# BW1098FFC_TopLevel.net
KiCad netlist of a schematic drawn in Altium Designer
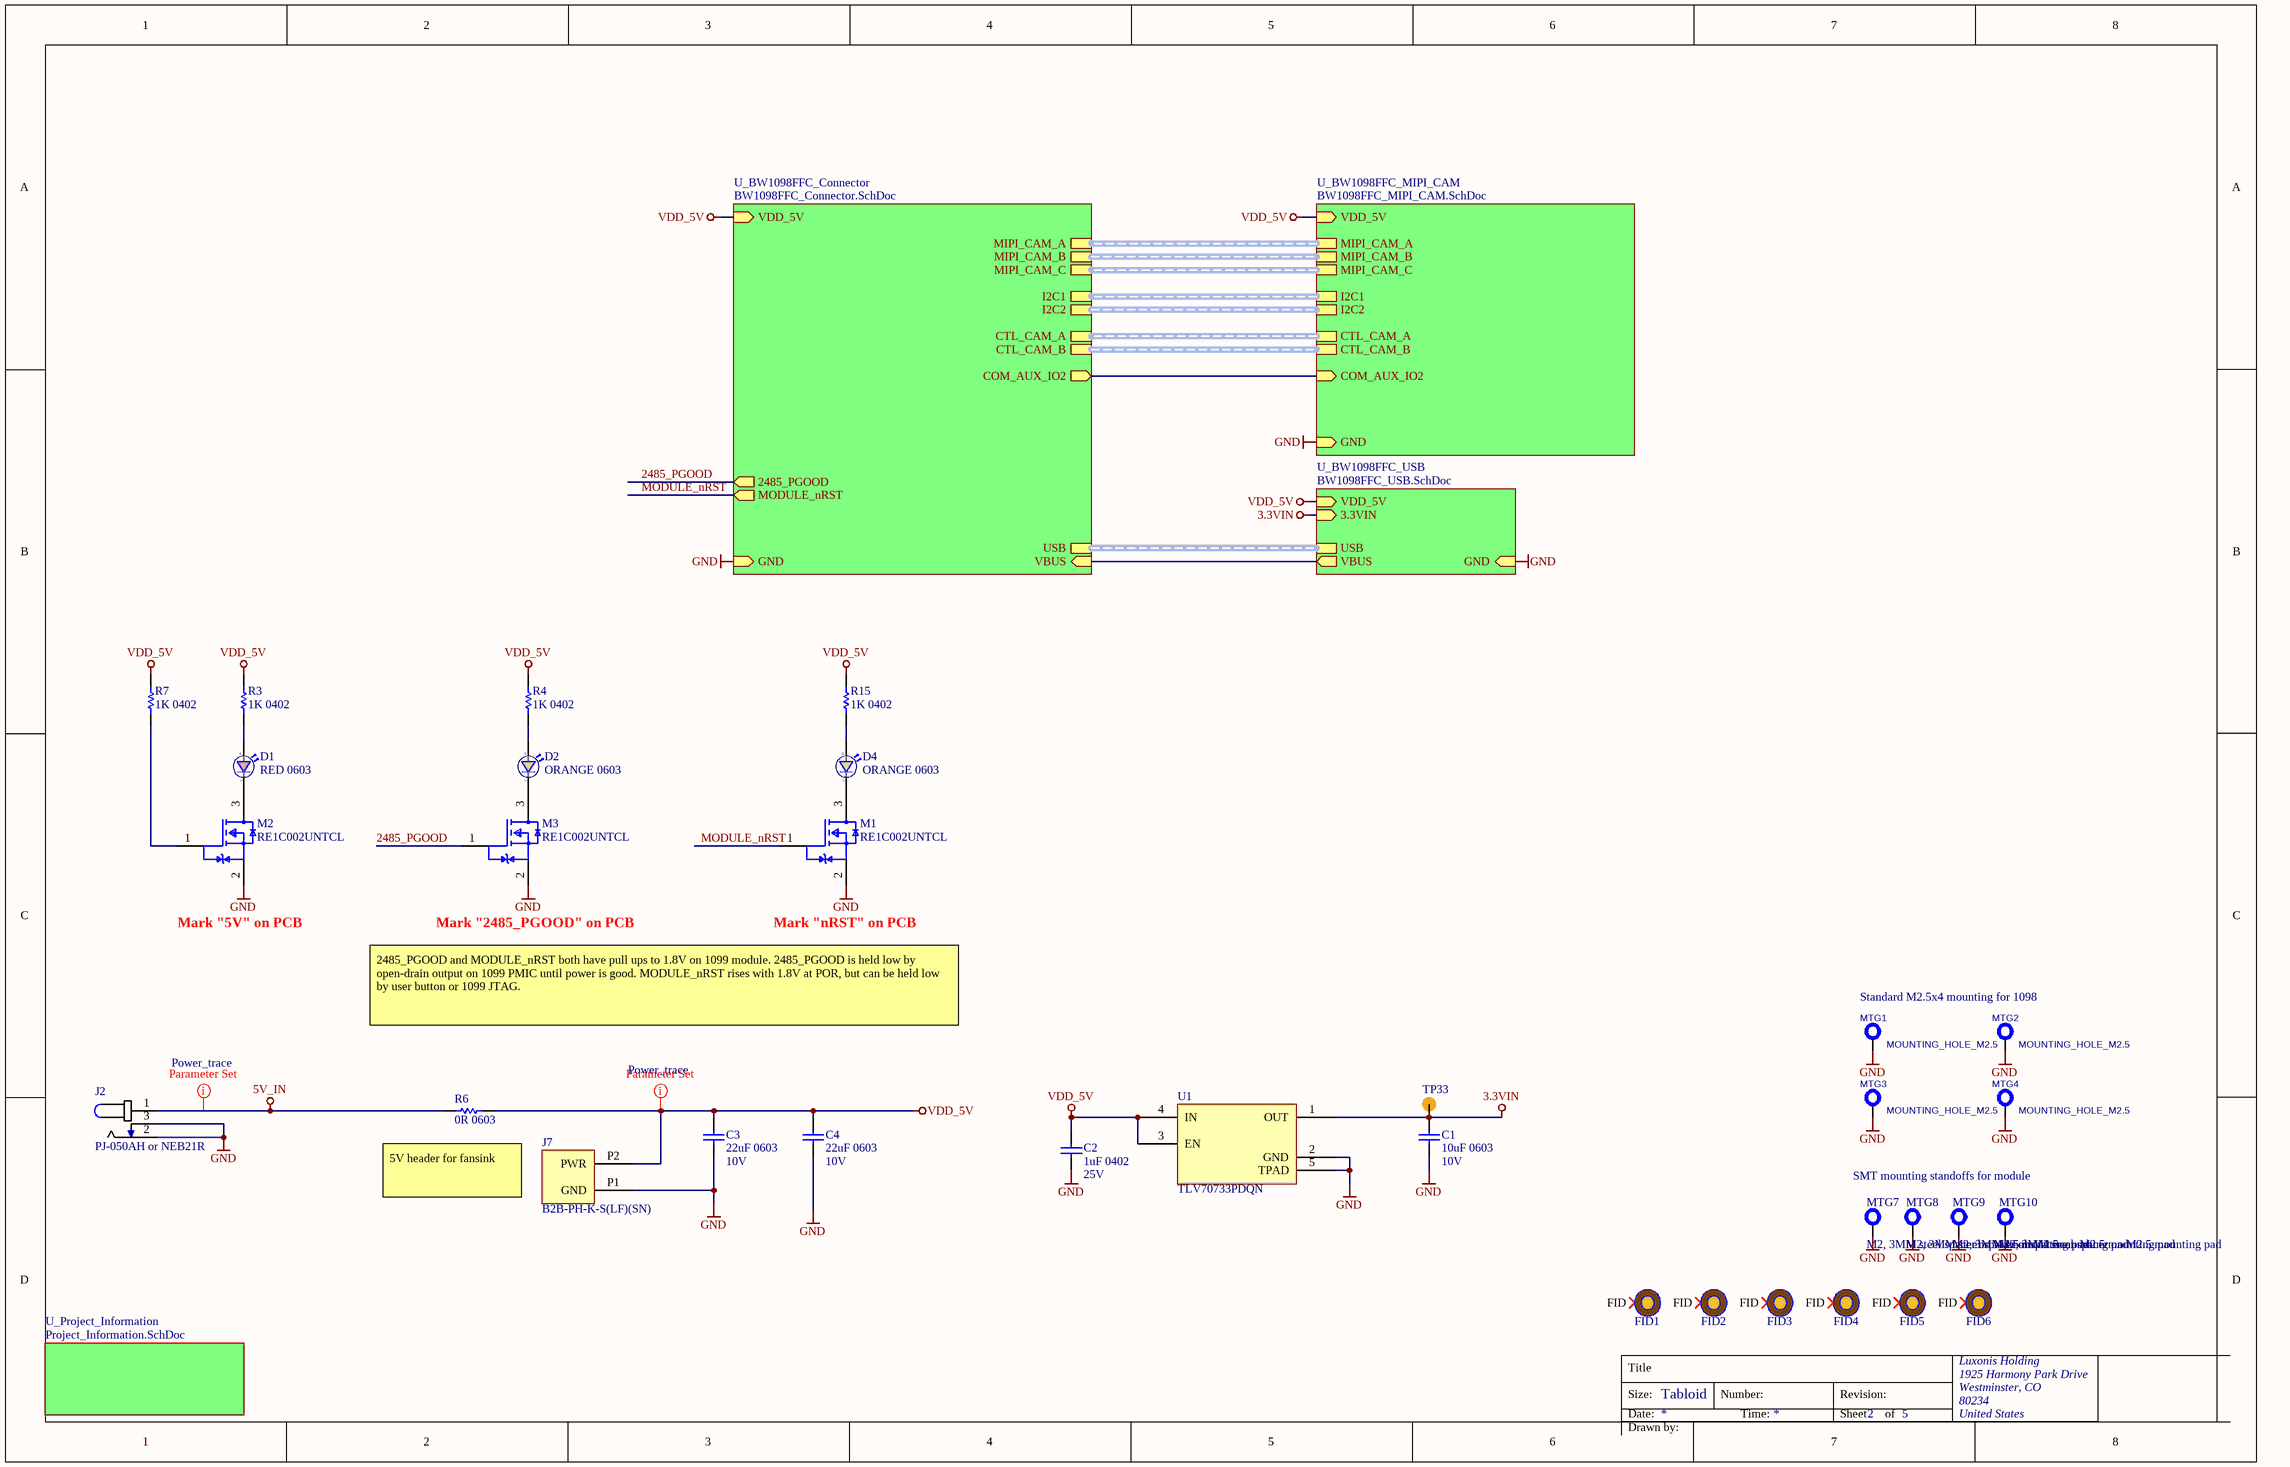
[diagram p0: BW1098FFC_TopLevel.SchDoc]

(export (version "E")
  (design (tool "Eeschema 10.0.6"))
  (components
    (comp (ref "C1")
      (value "10uF 0603")
      (footprint "CAP_Altium_Vault_Generic:CAPC0603(1608)100_N")
      (description "CAP CER 10UF 10V X5R 0603 20%")
      (fields (field (name "TOLERANCE") "20%") (field (name "VOLTAGE RATING") "10V"))
      (libsource (lib "LuxonisMaster") (part "GRM188R61A106ME69D"))
    )
    (comp (ref "C2")
      (value "1uF 0402")
      (footprint "CAP_Altium_Vault_Generic:CAPC0402(1005)70_N")
      (description "CAP CER 1UF 25V X5R 0402 10%")
      (fields
        (field (name "TOLERANCE") "10%")
        (field (name "VOLTAGE") "25V")
        (field (name "VOLTAGE RATING") "25V")
      )
      (libsource (lib "LuxonisMaster") (part "GRM155R61E105KA12D"))
    )
    (comp (ref "C3")
      (value "22uF 0603")
      (footprint "CAP_Altium_Vault_Generic:CAPC0603(1608)100_N")
      (description "CAP CER 22UF 10V X5R 0603 20%")
      (fields (field (name "TOLERANCE") "20%") (field (name "VOLTAGE RATING") "10V"))
      (libsource (lib "LuxonisMaster") (part "GRM188R61A226ME15D"))
    )
    (comp (ref "C4")
      (value "22uF 0603")
      (footprint "CAP_Altium_Vault_Generic:CAPC0603(1608)100_N")
      (description "CAP CER 22UF 10V X5R 0603 20%")
      (fields (field (name "TOLERANCE") "20%") (field (name "VOLTAGE RATING") "10V"))
      (libsource (lib "LuxonisMaster") (part "GRM188R61A226ME15D"))
    )
    (comp (ref "D1")
      (value "RED 0603")
      (footprint "LuxonisMaster:SML_D1xx8W")
      (description "LED RED DIFFUSED 0603 SMD Red 620nm LED Indication - Discrete 2.2V 0603 (1608 Metric)")
      (libsource (lib "LuxonisMaster") (part "SML-D12U8WT86"))
    )
    (comp (ref "D2")
      (value "ORANGE 0603")
      (footprint "LuxonisMaster:SML_D1xx8W")
      (description "LED ORANGE DIFFUSED 0603 SMD Orange 605nm LED Indication - Discrete 2.2V 0603 (1608 Metric)")
      (libsource (lib "LuxonisMaster") (part "SML-D12D8WT86"))
    )
    (comp (ref "D4")
      (value "ORANGE 0603")
      (footprint "LuxonisMaster:SML_D1xx8W")
      (description "LED ORANGE DIFFUSED 0603 SMD Orange 605nm LED Indication - Discrete 2.2V 0603 (1608 Metric)")
      (libsource (lib "LuxonisMaster") (part "SML-D12D8WT86"))
    )
    (comp (ref "FID1")
      (value "FIDUCIAL_ROUND_1MM")
      (footprint "LuxonisMaster:FIDUCIAL_ROUND_1MM")
      (description "Fiducial with various available footprints")
      (libsource (lib "LuxonisMaster") (part "FIDUCIAL"))
    )
    (comp (ref "FID2")
      (value "FIDUCIAL_ROUND_1MM")
      (footprint "LuxonisMaster:FIDUCIAL_ROUND_1MM")
      (description "Fiducial with various available footprints")
      (libsource (lib "LuxonisMaster") (part "FIDUCIAL"))
    )
    (comp (ref "FID3")
      (value "FIDUCIAL_ROUND_1MM")
      (footprint "LuxonisMaster:FIDUCIAL_ROUND_1MM")
      (description "Fiducial with various available footprints")
      (libsource (lib "LuxonisMaster") (part "FIDUCIAL"))
    )
    (comp (ref "FID4")
      (value "FIDUCIAL_ROUND_1MM")
      (footprint "LuxonisMaster:FIDUCIAL_ROUND_1MM")
      (description "Fiducial with various available footprints")
      (libsource (lib "LuxonisMaster") (part "FIDUCIAL"))
    )
    (comp (ref "FID5")
      (value "FIDUCIAL_ROUND_1MM")
      (footprint "LuxonisMaster:FIDUCIAL_ROUND_1MM")
      (description "Fiducial with various available footprints")
      (libsource (lib "LuxonisMaster") (part "FIDUCIAL"))
    )
    (comp (ref "FID6")
      (value "FIDUCIAL_ROUND_1MM")
      (footprint "LuxonisMaster:FIDUCIAL_ROUND_1MM")
      (description "Fiducial with various available footprints")
      (libsource (lib "LuxonisMaster") (part "FIDUCIAL"))
    )
    (comp (ref "J2")
      (value "PJ-050AH or NEB21R")
      (footprint "LuxonisMaster:PJ-050AH/NEB21R_COMBO")
      (description "CONN POWER PIN 2 POS RA PTH Barrel jack 2.1mm x 5.5mm combo footprint")
      (libsource (lib "LuxonisMaster") (part "PJ-050AH/NEB21R_COMBO"))
    )
    (comp (ref "J7")
      (value "B2B-PH-K-S(LF)(SN)")
      (footprint "LuxonisMaster:B2B-PH-K-S(LF)(SN)")
      (description "CONN HEADER VERT 2POS 2MM")
      (libsource (lib "LuxonisMaster") (part "B2B-PH-K-S(LF)(SN)"))
    )
    (comp (ref "M1")
      (value "RE1C002UNTCL")
      (footprint "LuxonisMaster:RE1C002UNTCL")
      (description "MOSFET N-CH 20V 0.2A EMT3")
      (libsource (lib "LuxonisMaster") (part "RE1C002UNTCL"))
    )
    (comp (ref "M2")
      (value "RE1C002UNTCL")
      (footprint "LuxonisMaster:RE1C002UNTCL")
      (description "MOSFET N-CH 20V 0.2A EMT3")
      (libsource (lib "LuxonisMaster") (part "RE1C002UNTCL"))
    )
    (comp (ref "M3")
      (value "RE1C002UNTCL")
      (footprint "LuxonisMaster:RE1C002UNTCL")
      (description "MOSFET N-CH 20V 0.2A EMT3")
      (libsource (lib "LuxonisMaster") (part "RE1C002UNTCL"))
    )
    (comp (ref "MTG1")
      (value "MOUNTING_HOLE_M2.5")
      (footprint "LuxonisMaster:MOUNTING_HOLE_M2.5")
      (description "=CurrentFootprint")
      (libsource (lib "LuxonisMaster") (part "MP_Mounting-Holes"))
    )
    (comp (ref "MTG2")
      (value "MOUNTING_HOLE_M2.5")
      (footprint "LuxonisMaster:MOUNTING_HOLE_M2.5")
      (description "=CurrentFootprint")
      (libsource (lib "LuxonisMaster") (part "MP_Mounting-Holes"))
    )
    (comp (ref "MTG3")
      (value "MOUNTING_HOLE_M2.5")
      (footprint "LuxonisMaster:MOUNTING_HOLE_M2.5")
      (description "=CurrentFootprint")
      (libsource (lib "LuxonisMaster") (part "MP_Mounting-Holes"))
    )
    (comp (ref "MTG4")
      (value "MOUNTING_HOLE_M2.5")
      (footprint "LuxonisMaster:MOUNTING_HOLE_M2.5")
      (description "=CurrentFootprint")
      (libsource (lib "LuxonisMaster") (part "MP_Mounting-Holes"))
    )
    (comp (ref "MTG7")
      (value "M2, 3MM steel spacer on M2.5 mounting pad")
      (footprint "LuxonisMaster:9774030243R")
      (description "MP ROUND STANDOFF M2X0.4 STEEL 3MM")
      (libsource (lib "LuxonisMaster") (part "9774030243R"))
    )
    (comp (ref "MTG8")
      (value "M2, 3MM steel spacer on M2.5 mounting pad")
      (footprint "LuxonisMaster:9774030243R")
      (description "MP ROUND STANDOFF M2X0.4 STEEL 3MM")
      (libsource (lib "LuxonisMaster") (part "9774030243R"))
    )
    (comp (ref "MTG9")
      (value "M2, 3MM steel spacer on M2.5 mounting pad")
      (footprint "LuxonisMaster:9774030243R")
      (description "MP ROUND STANDOFF M2X0.4 STEEL 3MM")
      (libsource (lib "LuxonisMaster") (part "9774030243R"))
    )
    (comp (ref "MTG10")
      (value "M2, 3MM steel spacer on M2.5 mounting pad")
      (footprint "LuxonisMaster:9774030243R")
      (description "MP ROUND STANDOFF M2X0.4 STEEL 3MM")
      (libsource (lib "LuxonisMaster") (part "9774030243R"))
    )
    (comp (ref "R3")
      (value "1K 0402")
      (footprint "RES_Altium_Vault_Generic:RESC0402(1005)_N")
      (fields (field (name "TOLERANCE") "1%"))
      (libsource (lib "LuxonisMaster") (part "RC0402FR-071KL"))
    )
    (comp (ref "R4")
      (value "1K 0402")
      (footprint "RES_Altium_Vault_Generic:RESC0402(1005)_N")
      (fields (field (name "TOLERANCE") "1%"))
      (libsource (lib "LuxonisMaster") (part "RC0402FR-071KL"))
    )
    (comp (ref "R6")
      (value "0R 0603")
      (footprint "RES_Altium_Vault_Generic:RESC0603(1608)_N")
      (fields (field (name "TOLERANCE") "5%"))
      (libsource (lib "LuxonisMaster") (part "CRCW06030000Z0EA"))
    )
    (comp (ref "R7")
      (value "1K 0402")
      (footprint "RES_Altium_Vault_Generic:RESC0402(1005)_N")
      (fields (field (name "TOLERANCE") "1%"))
      (libsource (lib "LuxonisMaster") (part "RC0402FR-071KL"))
    )
    (comp (ref "R15")
      (value "1K 0402")
      (footprint "RES_Altium_Vault_Generic:RESC0402(1005)_N")
      (fields (field (name "TOLERANCE") "1%"))
      (libsource (lib "LuxonisMaster") (part "RC0402FR-071KL"))
    )
    (comp (ref "TP33")
      (value "TP100_200_NS")
      (footprint "LuxonisMaster:TP100_200_NS")
      (libsource (lib "LuxonisMaster") (part "TEST_POINT"))
    )
    (comp (ref "U1")
      (value "TLV70733PDQN")
      (footprint "LuxonisMaster:TLV70733PDQN")
      (description "IC REG LINEAR 3.3V 200MA 4X2SON Linear Voltage Regulator IC  1 Output  200mA 4-X2SON (1x1)")
      (libsource (lib "LuxonisMaster") (part "TLV70733PDQN"))
    )
  )
  (nets
    (net (code "1") (name "/2485_PGOOD") (class "Default")
      (node (ref "M3") (pin "1") (pinfunction "Gate_1") (pintype "passive"))
    )
    (net (code "10") (name "/MODULE_nRST") (class "Default")
      (node (ref "M1") (pin "1") (pinfunction "Gate_1") (pintype "passive"))
    )
    (net (code "13") (name "3.3VIN") (class "Default")
      (node (ref "C1") (pin "2") (pinfunction "2_2") (pintype "passive"))
      (node (ref "TP33") (pin "1") (pintype "passive"))
      (node (ref "U1") (pin "1") (pinfunction "OUT_1") (pintype "power_in"))
    )
    (net (code "14") (name "5V_IN") (class "Default")
      (node (ref "J2") (pin "1") (pinfunction "1_1") (pintype "passive"))
      (node (ref "R6") (pin "1") (pinfunction "1_1") (pintype "passive"))
    )
    (net (code "15") (name "GND") (class "Default")
      (node (ref "C1") (pin "1") (pinfunction "1_1") (pintype "passive"))
      (node (ref "C2") (pin "1") (pinfunction "1_1") (pintype "passive"))
      (node (ref "C3") (pin "1") (pinfunction "1_1") (pintype "passive"))
      (node (ref "C4") (pin "1") (pinfunction "1_1") (pintype "passive"))
      (node (ref "J2") (pin "2") (pinfunction "2_2") (pintype "passive"))
      (node (ref "J2") (pin "3") (pinfunction "3_3") (pintype "passive"))
      (node (ref "J7") (pin "P1") (pinfunction "GND_P1") (pintype "passive"))
      (node (ref "M1") (pin "2") (pinfunction "Source_2") (pintype "passive"))
      (node (ref "M2") (pin "2") (pinfunction "Source_2") (pintype "passive"))
      (node (ref "M3") (pin "2") (pinfunction "Source_2") (pintype "passive"))
      (node (ref "MTG1") (pin "1") (pintype "passive"))
      (node (ref "MTG10") (pin "1") (pintype "passive"))
      (node (ref "MTG2") (pin "1") (pintype "passive"))
      (node (ref "MTG3") (pin "1") (pintype "passive"))
      (node (ref "MTG4") (pin "1") (pintype "passive"))
      (node (ref "MTG7") (pin "1") (pintype "passive"))
      (node (ref "MTG8") (pin "1") (pintype "passive"))
      (node (ref "MTG9") (pin "1") (pintype "passive"))
      (node (ref "U1") (pin "2") (pinfunction "GND_2") (pintype "power_in"))
      (node (ref "U1") (pin "5") (pinfunction "TPAD_5") (pintype "passive"))
    )
    (net (code "16") (name "Net-(D1-A)") (class "Default")
      (node (ref "D1") (pin "2") (pinfunction "A_2") (pintype "passive"))
      (node (ref "R3") (pin "1") (pinfunction "1_1") (pintype "passive"))
    )
    (net (code "17") (name "Net-(D1-C)") (class "Default")
      (node (ref "D1") (pin "1") (pinfunction "C_1") (pintype "passive"))
      (node (ref "M2") (pin "3") (pinfunction "Drain_3") (pintype "passive"))
    )
    (net (code "18") (name "Net-(D2-A)") (class "Default")
      (node (ref "D2") (pin "2") (pinfunction "A_2") (pintype "passive"))
      (node (ref "R4") (pin "1") (pinfunction "1_1") (pintype "passive"))
    )
    (net (code "19") (name "Net-(D2-C)") (class "Default")
      (node (ref "D2") (pin "1") (pinfunction "C_1") (pintype "passive"))
      (node (ref "M3") (pin "3") (pinfunction "Drain_3") (pintype "passive"))
    )
    (net (code "20") (name "Net-(D4-A)") (class "Default")
      (node (ref "D4") (pin "2") (pinfunction "A_2") (pintype "passive"))
      (node (ref "R15") (pin "1") (pinfunction "1_1") (pintype "passive"))
    )
    (net (code "21") (name "Net-(D4-C)") (class "Default")
      (node (ref "D4") (pin "1") (pinfunction "C_1") (pintype "passive"))
      (node (ref "M1") (pin "3") (pinfunction "Drain_3") (pintype "passive"))
    )
    (net (code "22") (name "Net-(M2-Gate)") (class "Default")
      (node (ref "M2") (pin "1") (pinfunction "Gate_1") (pintype "passive"))
      (node (ref "R7") (pin "1") (pinfunction "1_1") (pintype "passive"))
    )
    (net (code "23") (name "VDD_5V") (class "Default")
      (node (ref "C2") (pin "2") (pinfunction "2_2") (pintype "passive"))
      (node (ref "C3") (pin "2") (pinfunction "2_2") (pintype "passive"))
      (node (ref "C4") (pin "2") (pinfunction "2_2") (pintype "passive"))
      (node (ref "J7") (pin "P2") (pinfunction "PWR_P2") (pintype "passive"))
      (node (ref "R15") (pin "2") (pinfunction "2_2") (pintype "passive"))
      (node (ref "R3") (pin "2") (pinfunction "2_2") (pintype "passive"))
      (node (ref "R4") (pin "2") (pinfunction "2_2") (pintype "passive"))
      (node (ref "R6") (pin "2") (pinfunction "2_2") (pintype "passive"))
      (node (ref "R7") (pin "2") (pinfunction "2_2") (pintype "passive"))
      (node (ref "U1") (pin "3") (pinfunction "EN_3") (pintype "power_in"))
      (node (ref "U1") (pin "4") (pinfunction "IN_4") (pintype "power_in"))
    )
    (net (code "24") (name "unconnected-(FID1-PadFID)") (class "Default")
      (node (ref "FID1") (pin "FID") (pinfunction "FID_FID") (pintype "input+no_connect"))
    )
    (net (code "25") (name "unconnected-(FID2-PadFID)") (class "Default")
      (node (ref "FID2") (pin "FID") (pinfunction "FID_FID") (pintype "input+no_connect"))
    )
    (net (code "26") (name "unconnected-(FID3-PadFID)") (class "Default")
      (node (ref "FID3") (pin "FID") (pinfunction "FID_FID") (pintype "input+no_connect"))
    )
    (net (code "27") (name "unconnected-(FID4-PadFID)") (class "Default")
      (node (ref "FID4") (pin "FID") (pinfunction "FID_FID") (pintype "input+no_connect"))
    )
    (net (code "28") (name "unconnected-(FID5-PadFID)") (class "Default")
      (node (ref "FID5") (pin "FID") (pinfunction "FID_FID") (pintype "input+no_connect"))
    )
    (net (code "29") (name "unconnected-(FID6-PadFID)") (class "Default")
      (node (ref "FID6") (pin "FID") (pinfunction "FID_FID") (pintype "input+no_connect"))
    )
  )
)
